# Sheet3.net
KiCad netlist of a schematic drawn in Altium Designer
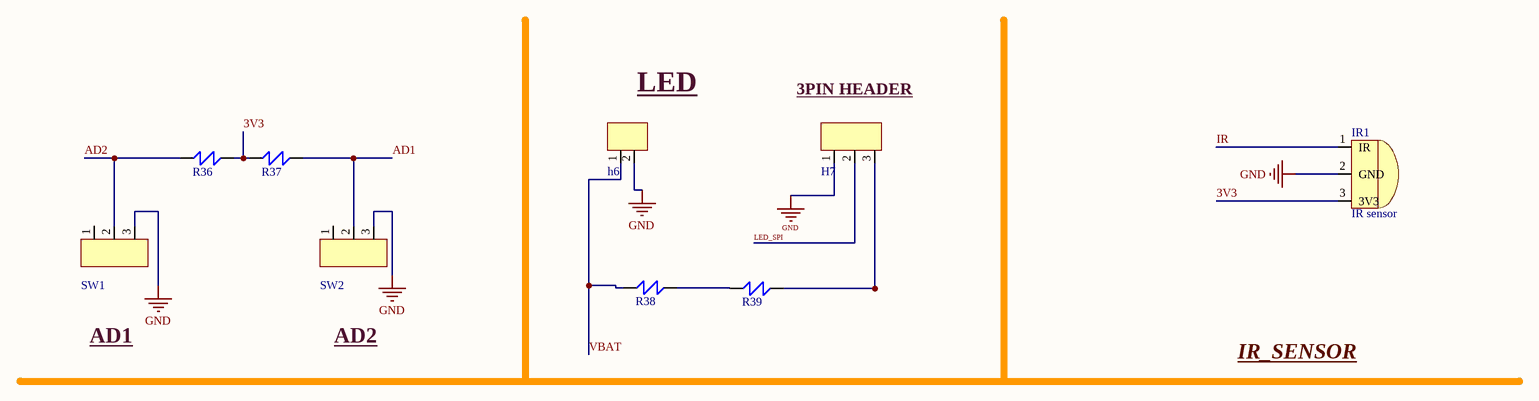
[diagram p0: Sheet3.SchDoc]

(export (version "E")
  (design (tool "Eeschema 10.0.6"))
  (components
    (comp (ref "h6")
      (value "HEADER/2mm")
      (footprint "Header2")
      (description "2pin / 2mm")
      (libsource (lib "Schlib1") (part "HEADER/2mm"))
    )
    (comp (ref "H7")
      (value "HEADER")
      (footprint "header3")
      (description "HEADER 2MM 3PIN")
      (libsource (lib "Schlib1") (part "HEADER/3PIN"))
    )
    (comp (ref "IR1")
      (value "IR sensor")
      (footprint "IR SENSOR")
      (libsource (lib "Schlib1") (part "IR Sensor"))
    )
    (comp (ref "R36")
      (value "4.7K")
      (footprint "R_22K")
      (description "4.7K SMD Resistance")
      (libsource (lib "Schlib1") (part "RES_1"))
    )
    (comp (ref "R37")
      (value "4.7K")
      (footprint "R_22K")
      (description "4.7K SMD Resistance")
      (libsource (lib "Schlib1") (part "RES_1"))
    )
    (comp (ref "R38")
      (value "22K")
      (footprint "R_22R")
      (description "22R SMD Resistance")
      (libsource (lib "Schlib1") (part "RES_15"))
    )
    (comp (ref "R39")
      (value "22K")
      (footprint "R_22R")
      (description "22R SMD Resistance")
      (libsource (lib "Schlib1") (part "RES_15"))
    )
    (comp (ref "SW1") (value "B50KS") (footprint "VR2/50K") (libsource (lib "Schlib1") (part "B50KS")))
    (comp (ref "SW2") (value "B50KS") (footprint "VR2/50K") (libsource (lib "Schlib1") (part "B50KS")))
  )
  (nets
    (net (code "1") (name "/3V3") (class "Default")
      (node (ref "IR1") (pin "3") (pinfunction "3V3_3") (pintype "passive"))
      (node (ref "R36") (pin "1") (pinfunction "1_1") (pintype "passive"))
      (node (ref "R37") (pin "2") (pinfunction "2_2") (pintype "passive"))
    )
    (net (code "2") (name "/AD1") (class "Default")
      (node (ref "R37") (pin "1") (pinfunction "1_1") (pintype "passive"))
      (node (ref "SW2") (pin "2") (pinfunction "2_2") (pintype "passive"))
    )
    (net (code "3") (name "/AD2") (class "Default")
      (node (ref "R36") (pin "2") (pinfunction "2_2") (pintype "passive"))
      (node (ref "SW1") (pin "2") (pinfunction "2_2") (pintype "passive"))
    )
    (net (code "4") (name "/IR") (class "Default")
      (node (ref "IR1") (pin "1") (pinfunction "IR_1") (pintype "passive"))
    )
    (net (code "5") (name "/LED_SPI") (class "Default")
      (node (ref "H7") (pin "2") (pinfunction "2_2") (pintype "passive"))
    )
    (net (code "6") (name "/VBAT") (class "Default")
      (node (ref "R38") (pin "2") (pinfunction "2_2") (pintype "passive"))
      (node (ref "h6") (pin "1") (pinfunction "1_1") (pintype "passive"))
    )
    (net (code "7") (name "GND") (class "Default")
      (node (ref "H7") (pin "1") (pinfunction "1_1") (pintype "passive"))
      (node (ref "IR1") (pin "2") (pinfunction "GND_2") (pintype "passive"))
      (node (ref "SW1") (pin "3") (pinfunction "3_3") (pintype "passive"))
      (node (ref "SW2") (pin "3") (pinfunction "3_3") (pintype "passive"))
      (node (ref "h6") (pin "2") (pinfunction "2_2") (pintype "passive"))
    )
    (net (code "8") (name "Net-(H7-Pad3)") (class "Default")
      (node (ref "H7") (pin "3") (pinfunction "3_3") (pintype "passive"))
      (node (ref "R39") (pin "1") (pinfunction "1_1") (pintype "passive"))
    )
    (net (code "9") (name "Net-(R38-Pad1)") (class "Default")
      (node (ref "R38") (pin "1") (pinfunction "1_1") (pintype "passive"))
      (node (ref "R39") (pin "2") (pinfunction "2_2") (pintype "passive"))
    )
    (net (code "10") (name "unconnected-(SW1-Pad1)") (class "Default")
      (node (ref "SW1") (pin "1") (pinfunction "1_1") (pintype "passive"))
    )
    (net (code "11") (name "unconnected-(SW2-Pad1)") (class "Default")
      (node (ref "SW2") (pin "1") (pinfunction "1_1") (pintype "passive"))
    )
  )
)
